# 6-_PCB.net
KiCad netlist of a schematic drawn in EasyEDA Pro
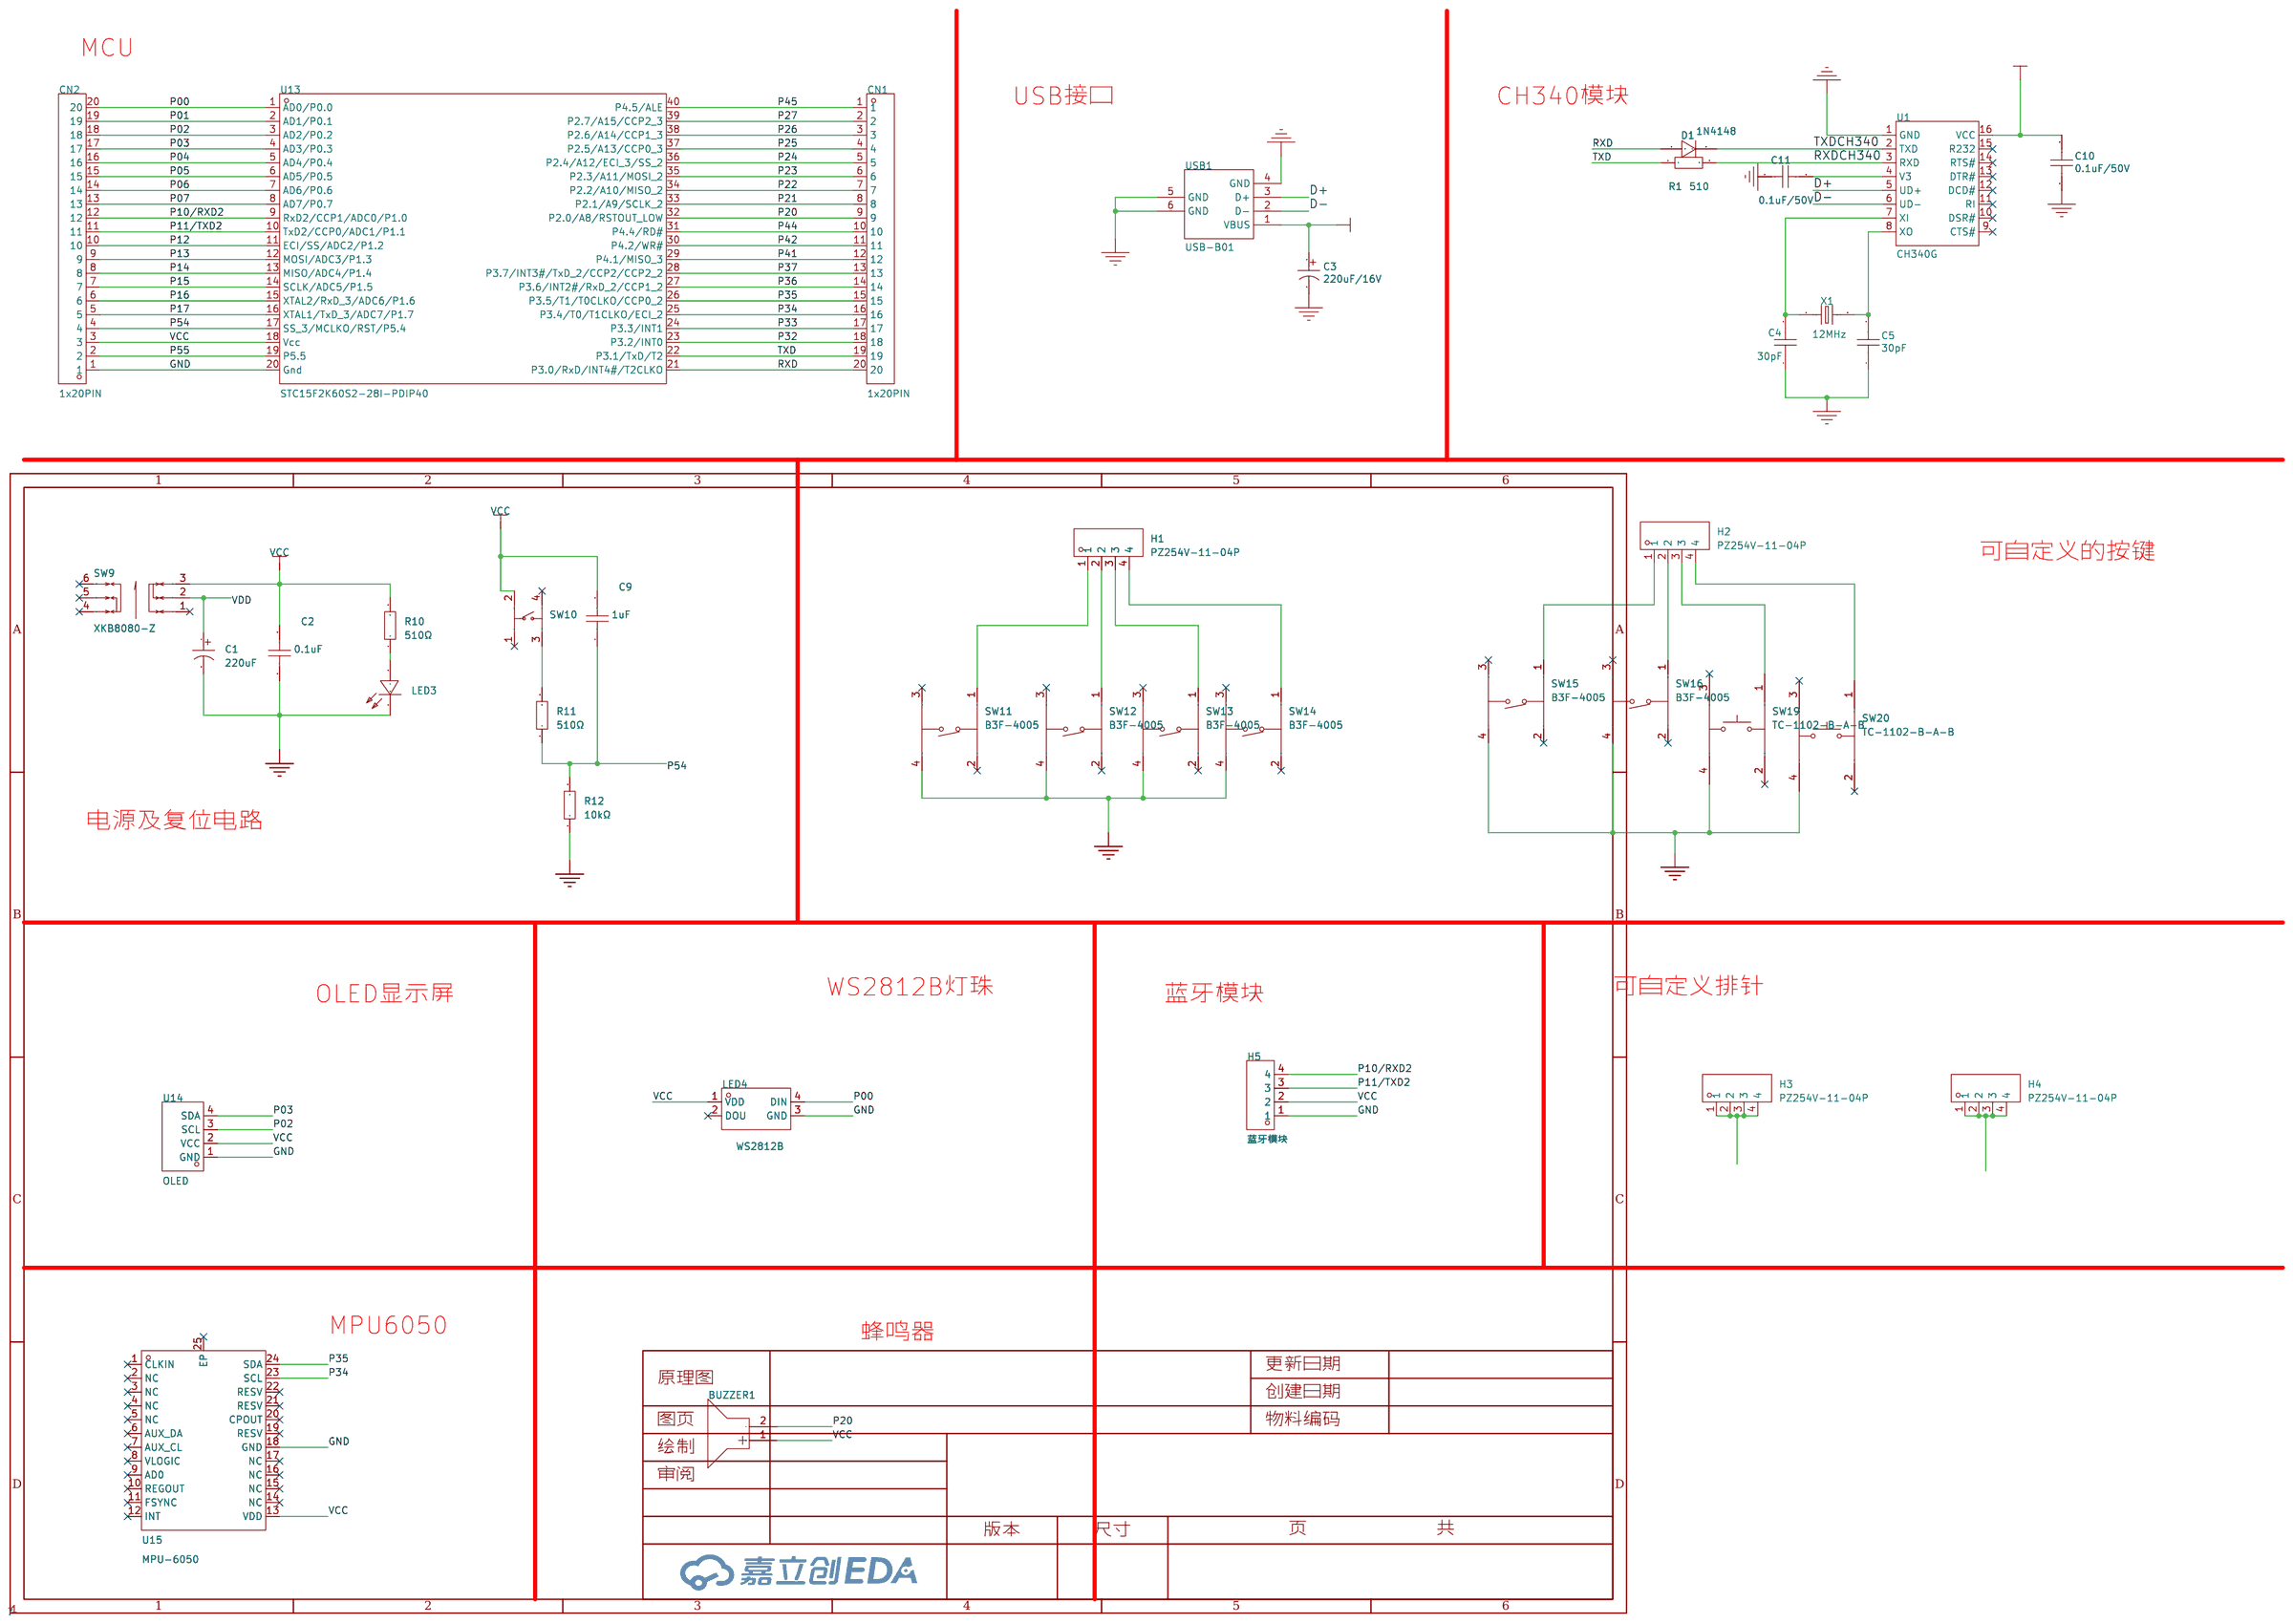
[diagram p0: schematic sheet]

(export (version "E")
  (design (tool "Eeschema 10.0.6"))
  (components
    (comp (ref "BUZZER1")
      (value "3kHz")
      (footprint "easyedapro:BUZ-TH_BD9.0-P5.00-D0.6-FD")
      (description "驱动方式:有源(内含驱动线路);构造类型:电磁式;频率:3kHz;声压(SPL):85dB@10cm;")
      (fields (field (name "Manufacturer Part") "HNB09A03") (field (name "Manufacturer") "华能"))
      (libsource (lib "easyedapro") (part "HNB09A03"))
    )
    (comp (ref "C1")
      (value "220uF")
      (footprint "easyedapro:CAP-TH_BD6.3-P2.50-D1.0-FD")
      (description "容值:220uF;精度:±20%;额定电压:10V;纹波电流:-;等效串联电阻:-;")
      (fields
        (field (name "Manufacturer Part") "ZF227M010E07RR0VH4FP0")
        (field (name "Manufacturer") "CX(承兴)")
      )
      (libsource (lib "easyedapro") (part "220uF 10V 6.3*7"))
    )
    (comp (ref "C2")
      (value "0.1uF")
      (footprint "easyedapro:CAP-TH_L5.0-W2.5-P5.08-D0.7")
      (description "容值:33pF;精度:±5%;额定电压:50V;温度系数:NP0;")
      (fields
        (field (name "Manufacturer Part") "CC1H330JC74DCH4B10MN")
        (field (name "Manufacturer") "Dersonic(德尔创)")
      )
      (libsource (lib "easyedapro") (part "CC1H330JC74DCH4B10MN"))
    )
    (comp (ref "C3")
      (value "220uF/16V")
      (footprint "easyedapro:CAP-TH_BD6.3-P2.50-D1.0-FD")
      (fields (field (name "Manufacturer Part") "SS-101M1ASA-0605") (field (name "Manufacturer") "Lelon"))
      (libsource (lib "easyedapro") (part "100uF"))
    )
    (comp (ref "C4")
      (value "30pF")
      (footprint "easyedapro:CAP-TH_L5.0-W2.5-P2.54-D0.7")
      (description "±5% 50V  瓷片电容 直插")
      (fields (field (name "Manufacturer Part") "CC4-0805N300J500F3") (field (name "Manufacturer") "FH"))
      (libsource (lib "easyedapro") (part "30pF"))
    )
    (comp (ref "C5")
      (value "30pF")
      (footprint "easyedapro:CAP-TH_L5.0-W2.5-P2.54-D0.7")
      (description "±5% 50V  瓷片电容 直插")
      (fields (field (name "Manufacturer Part") "CC4-0805N300J500F3") (field (name "Manufacturer") "FH"))
      (libsource (lib "easyedapro") (part "30pF"))
    )
    (comp (ref "C9")
      (value "1uF")
      (footprint "easyedapro:CAP-TH_L5.0-W2.5-P5.08-D0.7")
      (description "容值:33pF;精度:±5%;额定电压:50V;温度系数:NP0;")
      (fields
        (field (name "Manufacturer Part") "CC1H330JC74DCH4B10MN")
        (field (name "Manufacturer") "Dersonic(德尔创)")
      )
      (libsource (lib "easyedapro") (part "CC1H330JC74DCH4B10MN"))
    )
    (comp (ref "C10")
      (value "0.1uF/50V")
      (footprint "easyedapro:CAP-TH_L5.0-W2.5-P2.54-D0.7")
      (description "±5% 50V  瓷片电容 直插")
      (fields (field (name "Manufacturer Part") "CC4-0805N300J500F3") (field (name "Manufacturer") "FH"))
      (libsource (lib "easyedapro") (part "30pF"))
    )
    (comp (ref "C11")
      (value "0.1uF/50V")
      (footprint "easyedapro:CAP-TH_L5.0-W2.5-P2.54-D0.7")
      (description "±5% 50V  瓷片电容 直插")
      (fields (field (name "Manufacturer Part") "CC4-0805N300J500F3") (field (name "Manufacturer") "FH"))
      (libsource (lib "easyedapro") (part "30pF"))
    )
    (comp (ref "CN1")
      (value "1x20PIN")
      (footprint "easyedapro:hdr-th_20p-p2.54-v-m-4")
      (fields (field (name "Manufacturer") "HC(虹成电子)"))
      (libsource (lib "easyedapro") (part "hc-pz254-11.5l-1x20pz"))
    )
    (comp (ref "CN2")
      (value "1x20PIN")
      (footprint "easyedapro:hdr-th_20p-p2.54-v-m-4")
      (fields (field (name "Manufacturer") "HC(虹成电子)"))
      (libsource (lib "easyedapro") (part "hc-pz254-11.5l-1x20pz"))
    )
    (comp (ref "D1")
      (value "1N4148")
      (footprint "easyedapro:DO-35_BD2.0-L4.0-P8.00-D0.5-FD")
      (fields (field (name "Manufacturer") "ON Semicon"))
      (libsource (lib "easyedapro") (part "1N4148"))
    )
    (comp (ref "H1")
      (value "PZ254V-11-04P")
      (footprint "easyedapro:HDR-TH_4P-P2.54-V-M")
      (fields (field (name "Manufacturer") "XFCN(兴飞)"))
      (libsource (lib "easyedapro") (part "PZ254V-11-04P_C2691448"))
    )
    (comp (ref "H2")
      (value "PZ254V-11-04P")
      (footprint "easyedapro:HDR-TH_4P-P2.54-V-M")
      (fields (field (name "Manufacturer") "XFCN(兴飞)"))
      (libsource (lib "easyedapro") (part "PZ254V-11-04P_C2691448"))
    )
    (comp (ref "H3")
      (value "PZ254V-11-04P")
      (footprint "easyedapro:HDR-TH_4P-P2.54-V-M")
      (fields (field (name "Manufacturer") "XFCN(兴飞)"))
      (libsource (lib "easyedapro") (part "PZ254V-11-04P_C2691448"))
    )
    (comp (ref "H4")
      (value "PZ254V-11-04P")
      (footprint "easyedapro:HDR-TH_4P-P2.54-V-M")
      (fields (field (name "Manufacturer") "XFCN(兴飞)"))
      (libsource (lib "easyedapro") (part "PZ254V-11-04P_C2691448"))
    )
    (comp (ref "H5")
      (value "蓝牙模块")
      (footprint "easyedapro:HDR-TH_4P-P2.54-V-M")
      (fields (field (name "Manufacturer") "XFCN(兴飞)"))
      (libsource (lib "easyedapro") (part "PZ254V-11-04P_C2691448"))
    )
    (comp (ref "LED3")
      (value "LED1")
      (footprint "easyedapro:LED-TH_BD4.0-P2.50-RD")
      (fields (field (name "Manufacturer") "EVERLIGHT(亿光)"))
      (libsource (lib "easyedapro") (part "204-10SDRD/S530-A3/F182-68"))
    )
    (comp (ref "LED4")
      (value "WS2812B")
      (footprint "easyedapro:LED-SMD_4P-L5.0-W5.0-BL_XL-5050RGBC")
      (description "5050七彩幻彩透明贴片LED灯珠 5050 幻彩透明四脚 ws2812B 内置驱动IC")
      (fields (field (name "Manufacturer") "XINGLIGHT(成兴光)"))
      (libsource (lib "easyedapro") (part "XL-5050RGBC-WS2812B"))
    )
    (comp (ref "R1")
      (value "510")
      (footprint "easyedapro:RES-TH_BD1.7-L3.5-P7.50-D0.5")
      (description "金属膜电阻/1/8W")
      (fields
        (field (name "Manufacturer Part") "EWWR0008J4K70T9")
        (field (name "Manufacturer") "ResistorToday")
      )
      (libsource (lib "easyedapro") (part "4.7K"))
    )
    (comp (ref "R10")
      (value "510Ω")
      (footprint "easyedapro:RES-TH_BD2.3-L3.7-P7.70-D0.9")
      (description "电阻类型:金属膜电阻;阻值:330Ω;精度:±1%;功率:125mW;温度系数:±350ppm/°C;")
      (fields (field (name "Manufacturer Part") "MF1/8W-330Ω±1%-OT52") (field (name "Manufacturer") "VO(翔胜)"))
      (libsource (lib "easyedapro") (part "MF1/8W-330Ω±1%-OT52"))
    )
    (comp (ref "R11")
      (value "510Ω")
      (footprint "easyedapro:RES-TH_BD2.3-L3.7-P7.70-D0.9")
      (description "电阻类型:金属膜电阻;阻值:330Ω;精度:±1%;功率:125mW;温度系数:±350ppm/°C;")
      (fields (field (name "Manufacturer Part") "MF1/8W-330Ω±1%-OT52") (field (name "Manufacturer") "VO(翔胜)"))
      (libsource (lib "easyedapro") (part "MF1/8W-330Ω±1%-OT52"))
    )
    (comp (ref "R12")
      (value "10kΩ")
      (footprint "easyedapro:RES-TH_BD2.3-L3.7-P7.70-D0.9")
      (description "电阻类型:金属膜电阻;阻值:330Ω;精度:±1%;功率:125mW;温度系数:±350ppm/°C;")
      (fields (field (name "Manufacturer Part") "MF1/8W-330Ω±1%-OT52") (field (name "Manufacturer") "VO(翔胜)"))
      (libsource (lib "easyedapro") (part "MF1/8W-330Ω±1%-OT52"))
    )
    (comp (ref "SW9")
      (value "XKB8080-Z")
      (footprint "easyedapro:SW-TH_6P-L8.0-W8.0-P2.50")
      (description "自锁/无锁:自锁;安装方式:直插;触点电流:100mA;额定电压 (AC):250V;额定电压 (DC):30V;带灯:不带;作用力:160gf;机械寿命:10万次;")
      (fields (field (name "Manufacturer") "XKB Connectivity(中国星坤)"))
      (libsource (lib "easyedapro") (part "XKB8080-Z"))
    )
    (comp (ref "SW10")
      (value "KH-6X6X4.3H-TJ")
      (footprint "easyedapro:SW-TH_4P-L6.0-W6.0-P4.50-LS6.5")
      (fields (field (name "Manufacturer") "kinghelm(金航标)"))
      (libsource (lib "easyedapro") (part "KH-6X6X4.3H-TJ"))
    )
    (comp (ref "SW11")
      (value "B3F-4005")
      (footprint "easyedapro:SW-TH_4P-L12.0-W12.0-P5.00-LS12.5-EH")
      (description "电路结构:单刀单掷;按钮形状:圆形按钮;安装方式:直插;开关长度:12mm;开关宽度:12mm;开关高度:4.3mm;带灯:-;机械寿命:-;")
      (fields (field (name "Manufacturer") "OMRON(欧姆龙)"))
      (libsource (lib "easyedapro") (part "B3F-4005_C397283"))
    )
    (comp (ref "SW12")
      (value "B3F-4005")
      (footprint "easyedapro:SW-TH_4P-L12.0-W12.0-P5.00-LS12.5-EH")
      (description "电路结构:单刀单掷;按钮形状:圆形按钮;安装方式:直插;开关长度:12mm;开关宽度:12mm;开关高度:4.3mm;带灯:-;机械寿命:-;")
      (fields (field (name "Manufacturer") "OMRON(欧姆龙)"))
      (libsource (lib "easyedapro") (part "B3F-4005_C397283"))
    )
    (comp (ref "SW13")
      (value "B3F-4005")
      (footprint "easyedapro:SW-TH_4P-L12.0-W12.0-P5.00-LS12.5-EH")
      (description "电路结构:单刀单掷;按钮形状:圆形按钮;安装方式:直插;开关长度:12mm;开关宽度:12mm;开关高度:4.3mm;带灯:-;机械寿命:-;")
      (fields (field (name "Manufacturer") "OMRON(欧姆龙)"))
      (libsource (lib "easyedapro") (part "B3F-4005_C397283"))
    )
    (comp (ref "SW14")
      (value "B3F-4005")
      (footprint "easyedapro:SW-TH_4P-L12.0-W12.0-P5.00-LS12.5-EH")
      (description "电路结构:单刀单掷;按钮形状:圆形按钮;安装方式:直插;开关长度:12mm;开关宽度:12mm;开关高度:4.3mm;带灯:-;机械寿命:-;")
      (fields (field (name "Manufacturer") "OMRON(欧姆龙)"))
      (libsource (lib "easyedapro") (part "B3F-4005_C397283"))
    )
    (comp (ref "SW15")
      (value "B3F-4005")
      (footprint "easyedapro:SW-TH_4P-L12.0-W12.0-P5.00-LS12.5-EH")
      (description "电路结构:单刀单掷;按钮形状:圆形按钮;安装方式:直插;开关长度:12mm;开关宽度:12mm;开关高度:4.3mm;带灯:-;机械寿命:-;")
      (fields (field (name "Manufacturer") "OMRON(欧姆龙)"))
      (libsource (lib "easyedapro") (part "B3F-4005_C397283"))
    )
    (comp (ref "SW16")
      (value "B3F-4005")
      (footprint "easyedapro:SW-TH_4P-L12.0-W12.0-P5.00-LS12.5-EH")
      (description "电路结构:单刀单掷;按钮形状:圆形按钮;安装方式:直插;开关长度:12mm;开关宽度:12mm;开关高度:4.3mm;带灯:-;机械寿命:-;")
      (fields (field (name "Manufacturer") "OMRON(欧姆龙)"))
      (libsource (lib "easyedapro") (part "B3F-4005_C397283"))
    )
    (comp (ref "SW19")
      (value "TC-1102-B-A-B")
      (footprint "easyedapro:SW-TH_4P-L6.0-W6.0-P4.50-LS6.5")
      (fields (field (name "Manufacturer") "XKB Connectivity(中国星坤)"))
      (libsource (lib "easyedapro") (part "TC-1102-B-A-B"))
    )
    (comp (ref "SW20")
      (value "TC-1102-B-A-B")
      (footprint "easyedapro:SW-TH_4P-L6.0-W6.0-P4.50-LS6.5")
      (fields (field (name "Manufacturer") "XKB Connectivity(中国星坤)"))
      (libsource (lib "easyedapro") (part "TC-1102-B-A-B"))
    )
    (comp (ref "U1")
      (value "CH340G")
      (footprint "easyedapro:SOIC-16_L9.9-W3.9-P1.27-LS6.0-BL")
      (fields (field (name "Manufacturer") "WCH"))
      (libsource (lib "easyedapro") (part "CH340G"))
    )
    (comp (ref "U13")
      (value "STC15F2K60S2-28I-PDIP40")
      (footprint "easyedapro:DIP-40_L52.3-W13.9-P2.54-LS15.2-BL")
      (description "CPU内核:51系列;程序存储容量:60KB;RAM总容量:2KB;GPIO端口数量:38;工作电压范围:3.8V~5.5V;CPU最大主频:-;程序存储器类型:FLASH;")
      (fields (field (name "Manufacturer") "STC(宏晶)"))
      (libsource (lib "easyedapro") (part "STC15F2K60S2-28I-PDIP40"))
    )
    (comp (ref "U14")
      (value "OLED")
      (footprint "easyedapro:OLED-TH_L27.8-W27.2-P2.54_C9900033791")
      (description "主控芯片:SSD1315;接口类型:I2C;尺寸(inch):0.96;像素分辨率:128x64;")
      (fields (field (name "Manufacturer") "HS(汉昇)"))
      (libsource (lib "easyedapro") (part "HS96L03W2C03"))
    )
    (comp (ref "U15")
      (value "MPU-6050")
      (footprint "easyedapro:QFN-24_L4.0-W4.0-P0.50-BL-EP2.7")
      (description "传感器类型:加速度计陀螺仪;")
      (fields (field (name "Manufacturer") "TDK InvenSense(应美盛)"))
      (libsource (lib "easyedapro") (part "MPU-6050_C24112"))
    )
    (comp (ref "USB1")
      (value "USB-B01")
      (footprint "easyedapro:USB-B-TH_USB-B01")
      (description "卧式B型USB连接器/母座 90度 USB-B01")
      (fields (field (name "Manufacturer") "SOFNG"))
      (libsource (lib "easyedapro") (part "USB-B01"))
    )
    (comp (ref "X1")
      (value "12MHz")
      (footprint "easyedapro:HC-49US_L11.5-W4.5-P4.88")
      (fields (field (name "Manufacturer Part") "HC-49S12MHz20pF30PPM") (field (name "Manufacturer") "TAE"))
      (libsource (lib "easyedapro") (part "12MHz"))
    )
  )
  (nets
    (net (code "1") (name "/D+") (class "Default")
      (node (ref "U1") (pin "5") (pinfunction "UD+_5") (pintype "unspecified"))
      (node (ref "USB1") (pin "3") (pinfunction "D+_3") (pintype "unspecified"))
    )
    (net (code "2") (name "/D-") (class "Default")
      (node (ref "U1") (pin "6") (pinfunction "UD-_6") (pintype "unspecified"))
      (node (ref "USB1") (pin "2") (pinfunction "D-_2") (pintype "unspecified"))
    )
    (net (code "3") (name "/P00") (class "Default")
      (node (ref "CN2") (pin "20") (pinfunction "20_20") (pintype "unspecified"))
      (node (ref "LED4") (pin "4") (pinfunction "DIN_4") (pintype "unspecified"))
      (node (ref "U13") (pin "1") (pinfunction "AD0/P0.0_1") (pintype "unspecified"))
    )
    (net (code "4") (name "/P01") (class "Default")
      (node (ref "CN2") (pin "19") (pinfunction "19_19") (pintype "unspecified"))
      (node (ref "U13") (pin "2") (pinfunction "AD1/P0.1_2") (pintype "unspecified"))
    )
    (net (code "5") (name "/P02") (class "Default")
      (node (ref "CN2") (pin "18") (pinfunction "18_18") (pintype "unspecified"))
      (node (ref "U13") (pin "3") (pinfunction "AD2/P0.2_3") (pintype "unspecified"))
      (node (ref "U14") (pin "3") (pinfunction "SCL_3") (pintype "unspecified"))
    )
    (net (code "6") (name "/P03") (class "Default")
      (node (ref "CN2") (pin "17") (pinfunction "17_17") (pintype "unspecified"))
      (node (ref "U13") (pin "4") (pinfunction "AD3/P0.3_4") (pintype "unspecified"))
      (node (ref "U14") (pin "4") (pinfunction "SDA_4") (pintype "unspecified"))
    )
    (net (code "7") (name "/P04") (class "Default")
      (node (ref "CN2") (pin "16") (pinfunction "16_16") (pintype "unspecified"))
      (node (ref "U13") (pin "5") (pinfunction "AD4/P0.4_5") (pintype "unspecified"))
    )
    (net (code "8") (name "/P05") (class "Default")
      (node (ref "CN2") (pin "15") (pinfunction "15_15") (pintype "unspecified"))
      (node (ref "U13") (pin "6") (pinfunction "AD5/P0.5_6") (pintype "unspecified"))
    )
    (net (code "9") (name "/P06") (class "Default")
      (node (ref "CN2") (pin "14") (pinfunction "14_14") (pintype "unspecified"))
      (node (ref "U13") (pin "7") (pinfunction "AD6/P0.6_7") (pintype "unspecified"))
    )
    (net (code "10") (name "/P07") (class "Default")
      (node (ref "CN2") (pin "13") (pinfunction "13_13") (pintype "unspecified"))
      (node (ref "U13") (pin "8") (pinfunction "AD7/P0.7_8") (pintype "unspecified"))
    )
    (net (code "11") (name "/P10{slash}RXD2") (class "Default")
      (node (ref "CN2") (pin "12") (pinfunction "12_12") (pintype "unspecified"))
      (node (ref "H5") (pin "4") (pinfunction "4_4") (pintype "unspecified"))
      (node (ref "U13") (pin "9") (pinfunction "RxD2/CCP1/ADC0/P1.0_9") (pintype "unspecified"))
    )
    (net (code "12") (name "/P11{slash}TXD2") (class "Default")
      (node (ref "CN2") (pin "11") (pinfunction "11_11") (pintype "unspecified"))
      (node (ref "H5") (pin "3") (pinfunction "3_3") (pintype "unspecified"))
      (node (ref "U13") (pin "10") (pinfunction "TxD2/CCP0/ADC1/P1.1_10") (pintype "unspecified"))
    )
    (net (code "13") (name "/P12") (class "Default")
      (node (ref "CN2") (pin "10") (pinfunction "10_10") (pintype "unspecified"))
      (node (ref "U13") (pin "11") (pinfunction "ECI/SS/ADC2/P1.2_11") (pintype "unspecified"))
    )
    (net (code "14") (name "/P13") (class "Default")
      (node (ref "CN2") (pin "9") (pinfunction "9_9") (pintype "unspecified"))
      (node (ref "U13") (pin "12") (pinfunction "MOSI/ADC3/P1.3_12") (pintype "unspecified"))
    )
    (net (code "15") (name "/P14") (class "Default")
      (node (ref "CN2") (pin "8") (pinfunction "8_8") (pintype "unspecified"))
      (node (ref "U13") (pin "13") (pinfunction "MISO/ADC4/P1.4_13") (pintype "unspecified"))
    )
    (net (code "16") (name "/P15") (class "Default")
      (node (ref "CN2") (pin "7") (pinfunction "7_7") (pintype "unspecified"))
      (node (ref "U13") (pin "14") (pinfunction "SCLK/ADC5/P1.5_14") (pintype "unspecified"))
    )
    (net (code "17") (name "/P16") (class "Default")
      (node (ref "CN2") (pin "6") (pinfunction "6_6") (pintype "unspecified"))
      (node (ref "U13") (pin "15") (pinfunction "XTAL2/RxD_3/ADC6/P1.6_15") (pintype "unspecified"))
    )
    (net (code "18") (name "/P17") (class "Default")
      (node (ref "CN2") (pin "5") (pinfunction "5_5") (pintype "unspecified"))
      (node (ref "U13") (pin "16") (pinfunction "XTAL1/TxD_3/ADC7/P1.7_16") (pintype "unspecified"))
    )
    (net (code "19") (name "/P20") (class "Default")
      (node (ref "BUZZER1") (pin "2") (pinfunction "-_2") (pintype "unspecified"))
      (node (ref "CN1") (pin "9") (pinfunction "9_9") (pintype "unspecified"))
      (node (ref "U13") (pin "32") (pinfunction "P2.0/A8/RSTOUT_LOW_32") (pintype "unspecified"))
    )
    (net (code "20") (name "/P21") (class "Default")
      (node (ref "CN1") (pin "8") (pinfunction "8_8") (pintype "unspecified"))
      (node (ref "U13") (pin "33") (pinfunction "P2.1/A9/SCLK_2_33") (pintype "unspecified"))
    )
    (net (code "21") (name "/P22") (class "Default")
      (node (ref "CN1") (pin "7") (pinfunction "7_7") (pintype "unspecified"))
      (node (ref "U13") (pin "34") (pinfunction "P2.2/A10/MISO_2_34") (pintype "unspecified"))
    )
    (net (code "22") (name "/P23") (class "Default")
      (node (ref "CN1") (pin "6") (pinfunction "6_6") (pintype "unspecified"))
      (node (ref "U13") (pin "35") (pinfunction "P2.3/A11/MOSI_2_35") (pintype "unspecified"))
    )
    (net (code "23") (name "/P24") (class "Default")
      (node (ref "CN1") (pin "5") (pinfunction "5_5") (pintype "unspecified"))
      (node (ref "U13") (pin "36") (pinfunction "P2.4/A12/ECI_3/SS_2_36") (pintype "unspecified"))
    )
    (net (code "24") (name "/P25") (class "Default")
      (node (ref "CN1") (pin "4") (pinfunction "4_4") (pintype "unspecified"))
      (node (ref "U13") (pin "37") (pinfunction "P2.5/A13/CCP0_3_37") (pintype "unspecified"))
    )
    (net (code "25") (name "/P26") (class "Default")
      (node (ref "CN1") (pin "3") (pinfunction "3_3") (pintype "unspecified"))
      (node (ref "U13") (pin "38") (pinfunction "P2.6/A14/CCP1_3_38") (pintype "unspecified"))
    )
    (net (code "26") (name "/P27") (class "Default")
      (node (ref "CN1") (pin "2") (pinfunction "2_2") (pintype "unspecified"))
      (node (ref "U13") (pin "39") (pinfunction "P2.7/A15/CCP2_3_39") (pintype "unspecified"))
    )
    (net (code "27") (name "/P32") (class "Default")
      (node (ref "CN1") (pin "18") (pinfunction "18_18") (pintype "unspecified"))
      (node (ref "U13") (pin "23") (pinfunction "P3.2/INT0_23") (pintype "unspecified"))
    )
    (net (code "28") (name "/P33") (class "Default")
      (node (ref "CN1") (pin "17") (pinfunction "17_17") (pintype "unspecified"))
      (node (ref "U13") (pin "24") (pinfunction "P3.3/INT1_24") (pintype "unspecified"))
    )
    (net (code "29") (name "/P34") (class "Default")
      (node (ref "CN1") (pin "16") (pinfunction "16_16") (pintype "unspecified"))
      (node (ref "U13") (pin "25") (pinfunction "P3.4/T0/T1CLKO/ECI_2_25") (pintype "unspecified"))
      (node (ref "U15") (pin "23") (pinfunction "SCL_23") (pintype "unspecified"))
    )
    (net (code "30") (name "/P35") (class "Default")
      (node (ref "CN1") (pin "15") (pinfunction "15_15") (pintype "unspecified"))
      (node (ref "U13") (pin "26") (pinfunction "P3.5/T1/T0CLKO/CCP0_2_26") (pintype "unspecified"))
      (node (ref "U15") (pin "24") (pinfunction "SDA_24") (pintype "unspecified"))
    )
    (net (code "31") (name "/P36") (class "Default")
      (node (ref "CN1") (pin "14") (pinfunction "14_14") (pintype "unspecified"))
      (node (ref "U13") (pin "27") (pinfunction "P3.6/INT2#/RxD_2/CCP1_2_27") (pintype "unspecified"))
    )
    (net (code "32") (name "/P37") (class "Default")
      (node (ref "CN1") (pin "13") (pinfunction "13_13") (pintype "unspecified"))
      (node (ref "U13") (pin "28") (pinfunction "P3.7/INT3#/TxD_2/CCP2/CCP2_2_28") (pintype "unspecified"))
    )
    (net (code "33") (name "/P41") (class "Default")
      (node (ref "CN1") (pin "12") (pinfunction "12_12") (pintype "unspecified"))
      (node (ref "U13") (pin "29") (pinfunction "P4.1/MISO_3_29") (pintype "unspecified"))
    )
    (net (code "34") (name "/P42") (class "Default")
      (node (ref "CN1") (pin "11") (pinfunction "11_11") (pintype "unspecified"))
      (node (ref "U13") (pin "30") (pinfunction "P4.2/WR#_30") (pintype "unspecified"))
    )
    (net (code "35") (name "/P44") (class "Default")
      (node (ref "CN1") (pin "10") (pinfunction "10_10") (pintype "unspecified"))
      (node (ref "U13") (pin "31") (pinfunction "P4.4/RD#_31") (pintype "unspecified"))
    )
    (net (code "36") (name "/P45") (class "Default")
      (node (ref "CN1") (pin "1") (pinfunction "1_1") (pintype "unspecified"))
      (node (ref "U13") (pin "40") (pinfunction "P4.5/ALE_40") (pintype "unspecified"))
    )
    (net (code "37") (name "/P54") (class "Default")
      (node (ref "C9") (pin "1") (pinfunction "1_1") (pintype "unspecified"))
      (node (ref "CN2") (pin "4") (pinfunction "4_4") (pintype "unspecified"))
      (node (ref "R11") (pin "1") (pinfunction "1_1") (pintype "unspecified"))
      (node (ref "R12") (pin "2") (pinfunction "2_2") (pintype "unspecified"))
      (node (ref "U13") (pin "17") (pinfunction "SS_3/MCLKO/RST/P5.4_17") (pintype "unspecified"))
    )
    (net (code "38") (name "/P55") (class "Default")
      (node (ref "CN2") (pin "2") (pinfunction "2_2") (pintype "unspecified"))
      (node (ref "U13") (pin "19") (pinfunction "P5.5_19") (pintype "unspecified"))
    )
    (net (code "39") (name "/RXD") (class "Default")
      (node (ref "CN1") (pin "20") (pinfunction "20_20") (pintype "unspecified"))
      (node (ref "D1") (pin "1") (pinfunction "A_1") (pintype "unspecified"))
      (node (ref "U13") (pin "21") (pinfunction "P3.0/RxD/INT4#/T2CLKO_21") (pintype "unspecified"))
    )
    (net (code "40") (name "/RXDCH340") (class "Default")
      (node (ref "R1") (pin "2") (pinfunction "2_2") (pintype "unspecified"))
      (node (ref "U1") (pin "3") (pinfunction "RXD_3") (pintype "unspecified"))
    )
    (net (code "41") (name "/TXD") (class "Default")
      (node (ref "CN1") (pin "19") (pinfunction "19_19") (pintype "unspecified"))
      (node (ref "R1") (pin "1") (pinfunction "1_1") (pintype "unspecified"))
      (node (ref "U13") (pin "22") (pinfunction "P3.1/TxD/T2_22") (pintype "unspecified"))
    )
    (net (code "42") (name "/TXDCH340") (class "Default")
      (node (ref "D1") (pin "2") (pinfunction "K_2") (pintype "unspecified"))
      (node (ref "U1") (pin "2") (pinfunction "TXD_2") (pintype "unspecified"))
    )
    (net (code "43") (name "GND") (class "Default")
      (node (ref "C1") (pin "2") (pinfunction "2_2") (pintype "input"))
      (node (ref "C10") (pin "1") (pinfunction "1_1") (pintype "unspecified"))
      (node (ref "C11") (pin "1") (pinfunction "1_1") (pintype "unspecified"))
      (node (ref "C2") (pin "1") (pinfunction "1_1") (pintype "unspecified"))
      (node (ref "C3") (pin "2") (pinfunction "2_2") (pintype "unspecified"))
      (node (ref "C4") (pin "1") (pinfunction "1_1") (pintype "unspecified"))
      (node (ref "C5") (pin "1") (pinfunction "1_1") (pintype "unspecified"))
      (node (ref "CN2") (pin "1") (pinfunction "1_1") (pintype "unspecified"))
      (node (ref "H5") (pin "1") (pinfunction "1_1") (pintype "unspecified"))
      (node (ref "LED3") (pin "1") (pinfunction "C_1") (pintype "unspecified"))
      (node (ref "LED4") (pin "3") (pinfunction "GND_3") (pintype "unspecified"))
      (node (ref "R12") (pin "1") (pinfunction "1_1") (pintype "unspecified"))
      (node (ref "SW11") (pin "4") (pinfunction "4_4") (pintype "unspecified"))
      (node (ref "SW12") (pin "4") (pinfunction "4_4") (pintype "unspecified"))
      (node (ref "SW13") (pin "4") (pinfunction "4_4") (pintype "unspecified"))
      (node (ref "SW14") (pin "4") (pinfunction "4_4") (pintype "unspecified"))
      (node (ref "SW15") (pin "4") (pinfunction "4_4") (pintype "unspecified"))
      (node (ref "SW16") (pin "4") (pinfunction "4_4") (pintype "unspecified"))
      (node (ref "SW19") (pin "4") (pinfunction "4_4") (pintype "input"))
      (node (ref "SW20") (pin "4") (pinfunction "4_4") (pintype "input"))
      (node (ref "U1") (pin "1") (pinfunction "GND_1") (pintype "unspecified"))
      (node (ref "U13") (pin "20") (pinfunction "Gnd_20") (pintype "unspecified"))
      (node (ref "U14") (pin "1") (pinfunction "GND_1") (pintype "unspecified"))
      (node (ref "U15") (pin "18") (pinfunction "GND_18") (pintype "unspecified"))
      (node (ref "USB1") (pin "4") (pinfunction "GND_4") (pintype "unspecified"))
      (node (ref "USB1") (pin "5") (pinfunction "GND_5") (pintype "unspecified"))
      (node (ref "USB1") (pin "6") (pinfunction "GND_6") (pintype "unspecified"))
    )
    (net (code "44") (name "Net-(H1-Pad1)") (class "Default")
      (node (ref "H1") (pin "1") (pinfunction "1_1") (pintype "unspecified"))
      (node (ref "SW11") (pin "1") (pinfunction "1_1") (pintype "unspecified"))
    )
    (net (code "45") (name "Net-(H1-Pad2)") (class "Default")
      (node (ref "H1") (pin "2") (pinfunction "2_2") (pintype "unspecified"))
      (node (ref "SW12") (pin "1") (pinfunction "1_1") (pintype "unspecified"))
    )
    (net (code "46") (name "Net-(H1-Pad3)") (class "Default")
      (node (ref "H1") (pin "3") (pinfunction "3_3") (pintype "unspecified"))
      (node (ref "SW13") (pin "1") (pinfunction "1_1") (pintype "unspecified"))
    )
    (net (code "47") (name "Net-(H1-Pad4)") (class "Default")
      (node (ref "H1") (pin "4") (pinfunction "4_4") (pintype "unspecified"))
      (node (ref "SW14") (pin "1") (pinfunction "1_1") (pintype "unspecified"))
    )
    (net (code "48") (name "Net-(H2-Pad1)") (class "Default")
      (node (ref "H2") (pin "1") (pinfunction "1_1") (pintype "unspecified"))
      (node (ref "SW15") (pin "1") (pinfunction "1_1") (pintype "unspecified"))
    )
    (net (code "49") (name "Net-(H2-Pad2)") (class "Default")
      (node (ref "H2") (pin "2") (pinfunction "2_2") (pintype "unspecified"))
      (node (ref "SW16") (pin "1") (pinfunction "1_1") (pintype "unspecified"))
    )
    (net (code "50") (name "Net-(H2-Pad3)") (class "Default")
      (node (ref "H2") (pin "3") (pinfunction "3_3") (pintype "unspecified"))
      (node (ref "SW19") (pin "1") (pinfunction "1_1") (pintype "input"))
    )
    (net (code "51") (name "Net-(H2-Pad4)") (class "Default")
      (node (ref "H2") (pin "4") (pinfunction "4_4") (pintype "unspecified"))
      (node (ref "SW20") (pin "1") (pinfunction "1_1") (pintype "input"))
    )
    (net (code "52") (name "Net-(H3-Pad1)") (class "Default")
      (node (ref "H3") (pin "1") (pinfunction "1_1") (pintype "unspecified"))
      (node (ref "H3") (pin "2") (pinfunction "2_2") (pintype "unspecified"))
      (node (ref "H3") (pin "3") (pinfunction "3_3") (pintype "unspecified"))
      (node (ref "H3") (pin "4") (pinfunction "4_4") (pintype "unspecified"))
    )
    (net (code "53") (name "Net-(H4-Pad1)") (class "Default")
      (node (ref "H4") (pin "1") (pinfunction "1_1") (pintype "unspecified"))
      (node (ref "H4") (pin "2") (pinfunction "2_2") (pintype "unspecified"))
      (node (ref "H4") (pin "3") (pinfunction "3_3") (pintype "unspecified"))
      (node (ref "H4") (pin "4") (pinfunction "4_4") (pintype "unspecified"))
    )
    (net (code "54") (name "Net-(LED3-A)") (class "Default")
      (node (ref "LED3") (pin "2") (pinfunction "A_2") (pintype "unspecified"))
      (node (ref "R10") (pin "1") (pinfunction "1_1") (pintype "unspecified"))
    )
    (net (code "55") (name "Net-(R11-Pad2)") (class "Default")
      (node (ref "R11") (pin "2") (pinfunction "2_2") (pintype "unspecified"))
      (node (ref "SW10") (pin "3") (pinfunction "3_3") (pintype "unspecified"))
    )
    (net (code "56") (name "Net-(U1-V3)") (class "Default")
      (node (ref "C11") (pin "2") (pinfunction "2_2") (pintype "unspecified"))
      (node (ref "U1") (pin "4") (pinfunction "V3_4") (pintype "unspecified"))
    )
    (net (code "57") (name "Net-(U1-XI)") (class "Default")
      (node (ref "C4") (pin "2") (pinfunction "2_2") (pintype "unspecified"))
      (node (ref "U1") (pin "7") (pinfunction "XI_7") (pintype "unspecified"))
      (node (ref "X1") (pin "1") (pinfunction "1_1") (pintype "unspecified"))
    )
    (net (code "58") (name "Net-(U1-XO)") (class "Default")
      (node (ref "C5") (pin "2") (pinfunction "2_2") (pintype "unspecified"))
      (node (ref "U1") (pin "8") (pinfunction "XO_8") (pintype "unspecified"))
      (node (ref "X1") (pin "2") (pinfunction "2_2") (pintype "unspecified"))
    )
    (net (code "59") (name "VCC") (class "Default")
      (node (ref "BUZZER1") (pin "1") (pinfunction "+_1") (pintype "unspecified"))
      (node (ref "C2") (pin "2") (pinfunction "2_2") (pintype "unspecified"))
      (node (ref "C9") (pin "2") (pinfunction "2_2") (pintype "unspecified"))
      (node (ref "CN2") (pin "3") (pinfunction "3_3") (pintype "unspecified"))
      (node (ref "H5") (pin "2") (pinfunction "2_2") (pintype "unspecified"))
      (node (ref "LED4") (pin "1") (pinfunction "VDD_1") (pintype "unspecified"))
      (node (ref "R10") (pin "2") (pinfunction "2_2") (pintype "unspecified"))
      (node (ref "SW10") (pin "2") (pinfunction "2_2") (pintype "unspecified"))
      (node (ref "SW9") (pin "3") (pinfunction "3_3") (pintype "unspecified"))
      (node (ref "U13") (pin "18") (pinfunction "Vcc_18") (pintype "unspecified"))
      (node (ref "U14") (pin "2") (pinfunction "VCC_2") (pintype "unspecified"))
      (node (ref "U15") (pin "13") (pinfunction "VDD_13") (pintype "unspecified"))
    )
    (net (code "60") (name "VDD") (class "Default")
      (node (ref "C1") (pin "1") (pinfunction "1_1") (pintype "input"))
      (node (ref "C10") (pin "2") (pinfunction "2_2") (pintype "unspecified"))
      (node (ref "C3") (pin "1") (pinfunction "1_1") (pintype "unspecified"))
      (node (ref "SW9") (pin "2") (pinfunction "2_2") (pintype "unspecified"))
      (node (ref "U1") (pin "16") (pinfunction "VCC_16") (pintype "unspecified"))
      (node (ref "USB1") (pin "1") (pinfunction "VBUS_1") (pintype "unspecified"))
    )
    (net (code "61") (name "unconnected-(LED4-DOU-Pad2)") (class "Default")
      (node (ref "LED4") (pin "2") (pinfunction "DOU_2") (pintype "unspecified+no_connect"))
    )
    (net (code "62") (name "unconnected-(SW9-Pad1)") (class "Default")
      (node (ref "SW9") (pin "1") (pinfunction "1_1") (pintype "unspecified+no_connect"))
    )
    (net (code "63") (name "unconnected-(SW9-Pad4)") (class "Default")
      (node (ref "SW9") (pin "4") (pinfunction "4_4") (pintype "unspecified+no_connect"))
    )
    (net (code "64") (name "unconnected-(SW9-Pad5)") (class "Default")
      (node (ref "SW9") (pin "5") (pinfunction "5_5") (pintype "unspecified+no_connect"))
    )
    (net (code "65") (name "unconnected-(SW9-Pad6)") (class "Default")
      (node (ref "SW9") (pin "6") (pinfunction "6_6") (pintype "unspecified+no_connect"))
    )
    (net (code "66") (name "unconnected-(SW10-Pad1)") (class "Default")
      (node (ref "SW10") (pin "1") (pinfunction "1_1") (pintype "unspecified+no_connect"))
    )
    (net (code "67") (name "unconnected-(SW10-Pad4)") (class "Default")
      (node (ref "SW10") (pin "4") (pinfunction "4_4") (pintype "unspecified+no_connect"))
    )
    (net (code "68") (name "unconnected-(SW11-Pad2)") (class "Default")
      (node (ref "SW11") (pin "2") (pinfunction "2_2") (pintype "unspecified+no_connect"))
    )
    (net (code "69") (name "unconnected-(SW11-Pad3)") (class "Default")
      (node (ref "SW11") (pin "3") (pinfunction "3_3") (pintype "unspecified+no_connect"))
    )
    (net (code "70") (name "unconnected-(SW12-Pad2)") (class "Default")
      (node (ref "SW12") (pin "2") (pinfunction "2_2") (pintype "unspecified+no_connect"))
    )
    (net (code "71") (name "unconnected-(SW12-Pad3)") (class "Default")
      (node (ref "SW12") (pin "3") (pinfunction "3_3") (pintype "unspecified+no_connect"))
    )
    (net (code "72") (name "unconnected-(SW13-Pad2)") (class "Default")
      (node (ref "SW13") (pin "2") (pinfunction "2_2") (pintype "unspecified+no_connect"))
    )
    (net (code "73") (name "unconnected-(SW13-Pad3)") (class "Default")
      (node (ref "SW13") (pin "3") (pinfunction "3_3") (pintype "unspecified+no_connect"))
    )
    (net (code "74") (name "unconnected-(SW14-Pad2)") (class "Default")
      (node (ref "SW14") (pin "2") (pinfunction "2_2") (pintype "unspecified+no_connect"))
    )
    (net (code "75") (name "unconnected-(SW14-Pad3)") (class "Default")
      (node (ref "SW14") (pin "3") (pinfunction "3_3") (pintype "unspecified+no_connect"))
    )
    (net (code "76") (name "unconnected-(SW15-Pad2)") (class "Default")
      (node (ref "SW15") (pin "2") (pinfunction "2_2") (pintype "unspecified+no_connect"))
    )
    (net (code "77") (name "unconnected-(SW15-Pad3)") (class "Default")
      (node (ref "SW15") (pin "3") (pinfunction "3_3") (pintype "unspecified+no_connect"))
    )
    (net (code "78") (name "unconnected-(SW16-Pad2)") (class "Default")
      (node (ref "SW16") (pin "2") (pinfunction "2_2") (pintype "unspecified+no_connect"))
    )
    (net (code "79") (name "unconnected-(SW16-Pad3)") (class "Default")
      (node (ref "SW16") (pin "3") (pinfunction "3_3") (pintype "unspecified+no_connect"))
    )
    (net (code "80") (name "unconnected-(SW19-Pad2)") (class "Default")
      (node (ref "SW19") (pin "2") (pinfunction "2_2") (pintype "input+no_connect"))
    )
    (net (code "81") (name "unconnected-(SW19-Pad3)") (class "Default")
      (node (ref "SW19") (pin "3") (pinfunction "3_3") (pintype "input+no_connect"))
    )
    (net (code "82") (name "unconnected-(SW20-Pad2)") (class "Default")
      (node (ref "SW20") (pin "2") (pinfunction "2_2") (pintype "input+no_connect"))
    )
    (net (code "83") (name "unconnected-(SW20-Pad3)") (class "Default")
      (node (ref "SW20") (pin "3") (pinfunction "3_3") (pintype "input+no_connect"))
    )
    (net (code "84") (name "unconnected-(U1-CTS#-Pad9)") (class "Default")
      (node (ref "U1") (pin "9") (pinfunction "CTS#_9") (pintype "unspecified+no_connect"))
    )
    (net (code "85") (name "unconnected-(U1-DCD#-Pad12)") (class "Default")
      (node (ref "U1") (pin "12") (pinfunction "DCD#_12") (pintype "unspecified+no_connect"))
    )
    (net (code "86") (name "unconnected-(U1-DSR#-Pad10)") (class "Default")
      (node (ref "U1") (pin "10") (pinfunction "DSR#_10") (pintype "unspecified+no_connect"))
    )
    (net (code "87") (name "unconnected-(U1-DTR#-Pad13)") (class "Default")
      (node (ref "U1") (pin "13") (pinfunction "DTR#_13") (pintype "unspecified+no_connect"))
    )
    (net (code "88") (name "unconnected-(U1-R232-Pad15)") (class "Default")
      (node (ref "U1") (pin "15") (pinfunction "R232_15") (pintype "unspecified+no_connect"))
    )
    (net (code "89") (name "unconnected-(U1-RI-Pad11)") (class "Default")
      (node (ref "U1") (pin "11") (pinfunction "RI_11") (pintype "unspecified+no_connect"))
    )
    (net (code "90") (name "unconnected-(U1-RTS#-Pad14)") (class "Default")
      (node (ref "U1") (pin "14") (pinfunction "RTS#_14") (pintype "unspecified+no_connect"))
    )
    (net (code "91") (name "unconnected-(U15-AD0-Pad9)") (class "Default")
      (node (ref "U15") (pin "9") (pinfunction "AD0_9") (pintype "unspecified+no_connect"))
    )
    (net (code "92") (name "unconnected-(U15-AUX_CL-Pad7)") (class "Default")
      (node (ref "U15") (pin "7") (pinfunction "AUX_CL_7") (pintype "unspecified+no_connect"))
    )
    (net (code "93") (name "unconnected-(U15-AUX_DA-Pad6)") (class "Default")
      (node (ref "U15") (pin "6") (pinfunction "AUX_DA_6") (pintype "unspecified+no_connect"))
    )
    (net (code "94") (name "unconnected-(U15-CLKIN-Pad1)") (class "Default")
      (node (ref "U15") (pin "1") (pinfunction "CLKIN_1") (pintype "unspecified+no_connect"))
    )
    (net (code "95") (name "unconnected-(U15-CPOUT-Pad20)") (class "Default")
      (node (ref "U15") (pin "20") (pinfunction "CPOUT_20") (pintype "unspecified+no_connect"))
    )
    (net (code "96") (name "unconnected-(U15-EP-Pad25)") (class "Default")
      (node (ref "U15") (pin "25") (pinfunction "EP_25") (pintype "unspecified+no_connect"))
    )
    (net (code "97") (name "unconnected-(U15-FSYNC-Pad11)") (class "Default")
      (node (ref "U15") (pin "11") (pinfunction "FSYNC_11") (pintype "unspecified+no_connect"))
    )
    (net (code "98") (name "unconnected-(U15-INT-Pad12)") (class "Default")
      (node (ref "U15") (pin "12") (pinfunction "INT_12") (pintype "unspecified+no_connect"))
    )
    (net (code "99") (name "unconnected-(U15-NC-Pad2)") (class "Default")
      (node (ref "U15") (pin "2") (pinfunction "NC_2") (pintype "unspecified+no_connect"))
    )
    (net (code "100") (name "unconnected-(U15-NC-Pad3)") (class "Default")
      (node (ref "U15") (pin "3") (pinfunction "NC_3") (pintype "unspecified+no_connect"))
    )
    (net (code "101") (name "unconnected-(U15-NC-Pad4)") (class "Default")
      (node (ref "U15") (pin "4") (pinfunction "NC_4") (pintype "unspecified+no_connect"))
    )
    (net (code "102") (name "unconnected-(U15-NC-Pad5)") (class "Default")
      (node (ref "U15") (pin "5") (pinfunction "NC_5") (pintype "unspecified+no_connect"))
    )
    (net (code "103") (name "unconnected-(U15-NC-Pad14)") (class "Default")
      (node (ref "U15") (pin "14") (pinfunction "NC_14") (pintype "unspecified+no_connect"))
    )
    (net (code "104") (name "unconnected-(U15-NC-Pad15)") (class "Default")
      (node (ref "U15") (pin "15") (pinfunction "NC_15") (pintype "unspecified+no_connect"))
    )
    (net (code "105") (name "unconnected-(U15-NC-Pad16)") (class "Default")
      (node (ref "U15") (pin "16") (pinfunction "NC_16") (pintype "unspecified+no_connect"))
    )
    (net (code "106") (name "unconnected-(U15-NC-Pad17)") (class "Default")
      (node (ref "U15") (pin "17") (pinfunction "NC_17") (pintype "unspecified+no_connect"))
    )
    (net (code "107") (name "unconnected-(U15-REGOUT-Pad10)") (class "Default")
      (node (ref "U15") (pin "10") (pinfunction "REGOUT_10") (pintype "unspecified+no_connect"))
    )
    (net (code "108") (name "unconnected-(U15-RESV-Pad19)") (class "Default")
      (node (ref "U15") (pin "19") (pinfunction "RESV_19") (pintype "unspecified+no_connect"))
    )
    (net (code "109") (name "unconnected-(U15-RESV-Pad21)") (class "Default")
      (node (ref "U15") (pin "21") (pinfunction "RESV_21") (pintype "unspecified+no_connect"))
    )
    (net (code "110") (name "unconnected-(U15-RESV-Pad22)") (class "Default")
      (node (ref "U15") (pin "22") (pinfunction "RESV_22") (pintype "unspecified+no_connect"))
    )
    (net (code "111") (name "unconnected-(U15-VLOGIC-Pad8)") (class "Default")
      (node (ref "U15") (pin "8") (pinfunction "VLOGIC_8") (pintype "unspecified+no_connect"))
    )
  )
)
